# Connectors.net
KiCad netlist of a schematic drawn in Altium Designer
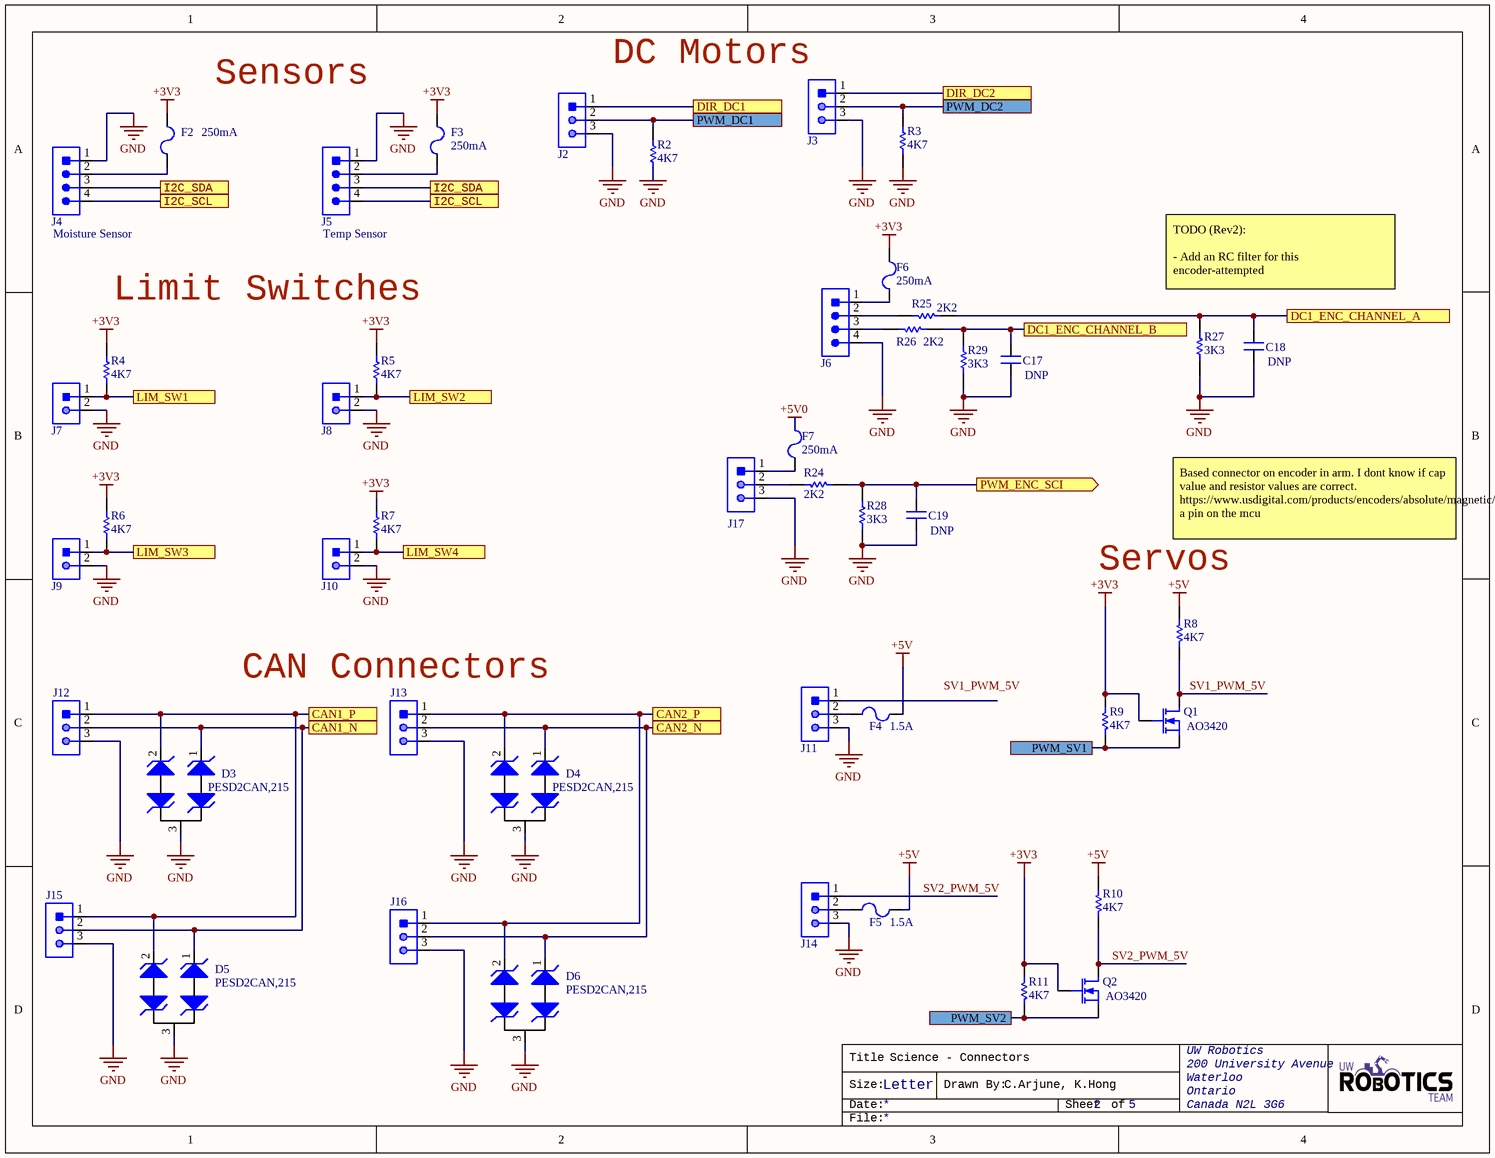
[diagram p0: Connectors.SchDoc]

(export (version "E")
  (design (tool "Eeschema 10.0.6"))
  (components
    (comp (ref "C17")
      (value "DNP")
      (footprint "CAPC0603(1608)55_N")
      (description "CAP CER 0.1UF 50V X7R 0603")
      (fields (field (name "MPN") "CC0603KRX7R9BB104") (field (name "MANUFACTURER") "Yageo"))
      (libsource (lib "UWRT_Schematic_Library_2020") (part "CAP_0.1uF_50V_0603"))
    )
    (comp (ref "C18")
      (value "DNP")
      (footprint "CAPC0603(1608)55_N")
      (description "CAP CER 0.1UF 50V X7R 0603")
      (fields (field (name "MPN") "CC0603KRX7R9BB104") (field (name "MANUFACTURER") "Yageo"))
      (libsource (lib "UWRT_Schematic_Library_2020") (part "CAP_0.1uF_50V_0603"))
    )
    (comp (ref "C19")
      (value "DNP")
      (footprint "CAPC0603(1608)55_N")
      (description "CAP CER 0.1UF 50V X7R 0603")
      (fields (field (name "MPN") "CC0603KRX7R9BB104") (field (name "MANUFACTURER") "Yageo"))
      (libsource (lib "UWRT_Schematic_Library_2020") (part "CAP_0.1uF_50V_0603"))
    )
    (comp (ref "D3")
      (value "TVS_DIODE_CAN")
      (footprint "TVS_DIODE_CAN")
      (description "TVS DIODE 24V 41V SOT323-3")
      (fields
        (field (name "MANUFACTURER") "Nexperia USA Inc.")
        (field (name "MANUFACTURER PART NUMBER") "PESD2CAN,215")
      )
      (libsource (lib "UWRT_Schematic_Library_2020") (part "TVS_DIODE_CAN"))
    )
    (comp (ref "D4")
      (value "TVS_DIODE_CAN")
      (footprint "TVS_DIODE_CAN")
      (description "TVS DIODE 24V 41V SOT323-3")
      (fields
        (field (name "MANUFACTURER") "Nexperia USA Inc.")
        (field (name "MANUFACTURER PART NUMBER") "PESD2CAN,215")
      )
      (libsource (lib "UWRT_Schematic_Library_2020") (part "TVS_DIODE_CAN"))
    )
    (comp (ref "D5")
      (value "TVS_DIODE_CAN")
      (footprint "TVS_DIODE_CAN")
      (description "TVS DIODE 24V 41V SOT323-3")
      (fields
        (field (name "MANUFACTURER") "Nexperia USA Inc.")
        (field (name "MANUFACTURER PART NUMBER") "PESD2CAN,215")
      )
      (libsource (lib "UWRT_Schematic_Library_2020") (part "TVS_DIODE_CAN"))
    )
    (comp (ref "D6")
      (value "TVS_DIODE_CAN")
      (footprint "TVS_DIODE_CAN")
      (description "TVS DIODE 24V 41V SOT323-3")
      (fields
        (field (name "MANUFACTURER") "Nexperia USA Inc.")
        (field (name "MANUFACTURER PART NUMBER") "PESD2CAN,215")
      )
      (libsource (lib "UWRT_Schematic_Library_2020") (part "TVS_DIODE_CAN"))
    )
    (comp (ref "F2")
      (value "FUSE_250mA_0603")
      (footprint "FUSE_0603")
      (description "FUSE SMD 250mA 32V")
      (fields (field (name "CURRENT RATING") "250mA"))
      (libsource (lib "UWRT_Schematic_Library_2020") (part "FUSE_250mA_0603"))
    )
    (comp (ref "F3")
      (value "FUSE_250mA_0603")
      (footprint "FUSE_0603")
      (description "FUSE SMD 250mA 32V")
      (fields (field (name "CURRENT RATING") "250mA"))
      (libsource (lib "UWRT_Schematic_Library_2020") (part "FUSE_250mA_0603"))
    )
    (comp (ref "F4")
      (value "FUSE_1.5A_0603")
      (footprint "FUSE_0603")
      (description "FUSE SMD 1.5A 32V")
      (fields (field (name "CURRENT RATING") "1.5A"))
      (libsource (lib "UWRT_Schematic_Library_2020") (part "FUSE_1.5A_0603"))
    )
    (comp (ref "F5")
      (value "FUSE_1.5A_0603")
      (footprint "FUSE_0603")
      (description "FUSE SMD 1.5A 32V")
      (fields (field (name "CURRENT RATING") "1.5A"))
      (libsource (lib "UWRT_Schematic_Library_2020") (part "FUSE_1.5A_0603"))
    )
    (comp (ref "F6")
      (value "FUSE_250mA_0603")
      (footprint "FUSE_0603")
      (description "FUSE SMD 250mA 32V")
      (fields (field (name "CURRENT RATING") "250mA"))
      (libsource (lib "UWRT_Schematic_Library_2020") (part "FUSE_250mA_0603"))
    )
    (comp (ref "F7")
      (value "FUSE_250mA_0603")
      (footprint "FUSE_0603")
      (description "FUSE SMD 250mA 32V")
      (fields (field (name "CURRENT RATING") "250mA"))
      (libsource (lib "UWRT_Schematic_Library_2020") (part "FUSE_250mA_0603"))
    )
    (comp (ref "J2")
      (value "CON_3M_SM4")
      (footprint "JST-B3B-SM4-TB")
      (description "CONN HEADER SMD 3POS 2MM")
      (fields
        (field (name "MANUFACTURER") "JST")
        (field (name "MANUFACTURER PART NUMBER") "B3B-PH-SM4-TB(LF)(SN)")
      )
      (libsource (lib "UWRT_Schematic_Library_2020") (part "CON_3M_SM4"))
    )
    (comp (ref "J3")
      (value "CON_3M_SM4")
      (footprint "JST-B3B-SM4-TB")
      (description "CONN HEADER SMD 3POS 2MM")
      (fields
        (field (name "MANUFACTURER") "JST")
        (field (name "MANUFACTURER PART NUMBER") "B3B-PH-SM4-TB(LF)(SN)")
      )
      (libsource (lib "UWRT_Schematic_Library_2020") (part "CON_3M_SM4"))
    )
    (comp (ref "J4")
      (value "Moisture Sensor")
      (footprint "JST-B4B-SM4-TB")
      (description "CONN HEADER SMD 4POS 2MM")
      (fields
        (field (name "MANUFACTURER") "JST")
        (field (name "MANUFACTURER PART NUMBER") "B4B-PH-SM4-TB(LF)(SN)")
      )
      (libsource (lib "UWRT_Schematic_Library_2020") (part "CON_4M_SM4"))
    )
    (comp (ref "J5")
      (value "Temp Sensor")
      (footprint "JST-B4B-SM4-TB")
      (description "CONN HEADER SMD 4POS 2MM")
      (fields
        (field (name "MANUFACTURER") "JST")
        (field (name "MANUFACTURER PART NUMBER") "B4B-PH-SM4-TB(LF)(SN)")
      )
      (libsource (lib "UWRT_Schematic_Library_2020") (part "CON_4M_SM4"))
    )
    (comp (ref "J6")
      (value "CON_4M_SM4")
      (footprint "JST-B4B-SM4-TB")
      (description "CONN HEADER SMD 4POS 2MM")
      (fields
        (field (name "MANUFACTURER") "JST")
        (field (name "MANUFACTURER PART NUMBER") "B4B-PH-SM4-TB(LF)(SN)")
      )
      (libsource (lib "UWRT_Schematic_Library_2020") (part "CON_4M_SM4"))
    )
    (comp (ref "J7")
      (value "CON_2M_SM4")
      (footprint "JST-B2B-SM4-TB")
      (description "CONN HEADER SMD 2POS 2MM")
      (fields
        (field (name "MANUFACTURER") "JST")
        (field (name "MANUFACTURER PART NUMBER") "B2B-PH-SM4-TB(LF)(SN)")
      )
      (libsource (lib "UWRT_Schematic_Library_2020") (part "CON_2M_SM4"))
    )
    (comp (ref "J8")
      (value "CON_2M_SM4")
      (footprint "JST-B2B-SM4-TB")
      (description "CONN HEADER SMD 2POS 2MM")
      (fields
        (field (name "MANUFACTURER") "JST")
        (field (name "MANUFACTURER PART NUMBER") "B2B-PH-SM4-TB(LF)(SN)")
      )
      (libsource (lib "UWRT_Schematic_Library_2020") (part "CON_2M_SM4"))
    )
    (comp (ref "J9")
      (value "CON_2M_SM4")
      (footprint "JST-B2B-SM4-TB")
      (description "CONN HEADER SMD 2POS 2MM")
      (fields
        (field (name "MANUFACTURER") "JST")
        (field (name "MANUFACTURER PART NUMBER") "B2B-PH-SM4-TB(LF)(SN)")
      )
      (libsource (lib "UWRT_Schematic_Library_2020") (part "CON_2M_SM4"))
    )
    (comp (ref "J10")
      (value "CON_2M_SM4")
      (footprint "JST-B2B-SM4-TB")
      (description "CONN HEADER SMD 2POS 2MM")
      (fields
        (field (name "MANUFACTURER") "JST")
        (field (name "MANUFACTURER PART NUMBER") "B2B-PH-SM4-TB(LF)(SN)")
      )
      (libsource (lib "UWRT_Schematic_Library_2020") (part "CON_2M_SM4"))
    )
    (comp (ref "J11")
      (value "CON_3M_SM4")
      (footprint "JST-B3B-SM4-TB")
      (description "CONN HEADER SMD 3POS 2MM")
      (fields
        (field (name "MANUFACTURER") "JST")
        (field (name "MANUFACTURER PART NUMBER") "B3B-PH-SM4-TB(LF)(SN)")
      )
      (libsource (lib "UWRT_Schematic_Library_2020") (part "CON_3M_SM4"))
    )
    (comp (ref "J12")
      (value "CON_3M_SM4")
      (footprint "JST-B3B-SM4-TB")
      (description "CONN HEADER SMD 3POS 2MM")
      (fields
        (field (name "MANUFACTURER") "JST")
        (field (name "MANUFACTURER PART NUMBER") "B3B-PH-SM4-TB(LF)(SN)")
      )
      (libsource (lib "UWRT_Schematic_Library_2020") (part "CON_3M_SM4"))
    )
    (comp (ref "J13")
      (value "CON_3M_SM4")
      (footprint "JST-B3B-SM4-TB")
      (description "CONN HEADER SMD 3POS 2MM")
      (fields
        (field (name "MANUFACTURER") "JST")
        (field (name "MANUFACTURER PART NUMBER") "B3B-PH-SM4-TB(LF)(SN)")
      )
      (libsource (lib "UWRT_Schematic_Library_2020") (part "CON_3M_SM4"))
    )
    (comp (ref "J14")
      (value "CON_3M_SM4")
      (footprint "JST-B3B-SM4-TB")
      (description "CONN HEADER SMD 3POS 2MM")
      (fields
        (field (name "MANUFACTURER") "JST")
        (field (name "MANUFACTURER PART NUMBER") "B3B-PH-SM4-TB(LF)(SN)")
      )
      (libsource (lib "UWRT_Schematic_Library_2020") (part "CON_3M_SM4"))
    )
    (comp (ref "J15")
      (value "CON_3M_SM4")
      (footprint "JST-B3B-SM4-TB")
      (description "CONN HEADER SMD 3POS 2MM")
      (fields
        (field (name "MANUFACTURER") "JST")
        (field (name "MANUFACTURER PART NUMBER") "B3B-PH-SM4-TB(LF)(SN)")
      )
      (libsource (lib "UWRT_Schematic_Library_2020") (part "CON_3M_SM4"))
    )
    (comp (ref "J16")
      (value "CON_3M_SM4")
      (footprint "JST-B3B-SM4-TB")
      (description "CONN HEADER SMD 3POS 2MM")
      (fields
        (field (name "MANUFACTURER") "JST")
        (field (name "MANUFACTURER PART NUMBER") "B3B-PH-SM4-TB(LF)(SN)")
      )
      (libsource (lib "UWRT_Schematic_Library_2020") (part "CON_3M_SM4"))
    )
    (comp (ref "J17")
      (value "CON_3M_SM4")
      (footprint "JST-B3B-SM4-TB")
      (description "CONN HEADER SMD 3POS 2MM")
      (fields
        (field (name "MANUFACTURER") "JST")
        (field (name "MANUFACTURER PART NUMBER") "B3B-PH-SM4-TB(LF)(SN)")
      )
      (libsource (lib "UWRT_Schematic_Library_2020") (part "CON_3M_SM4"))
    )
    (comp (ref "Q1")
      (value "NMOS_20V_6A")
      (footprint "NMOS_SOT23-3")
      (description "MOSFET N-CH 20V 6A SOT23")
      (fields (field (name "MPN") "AO3420") (field (name "MANUFACTURER") "Alpha & Omega"))
      (libsource (lib "UWRT_Schematic_Library_2020") (part "NMOS_20V_6A"))
    )
    (comp (ref "Q2")
      (value "NMOS_20V_6A")
      (footprint "NMOS_SOT23-3")
      (description "MOSFET N-CH 20V 6A SOT23")
      (fields (field (name "MPN") "AO3420") (field (name "MANUFACTURER") "Alpha & Omega"))
      (libsource (lib "UWRT_Schematic_Library_2020") (part "NMOS_20V_6A"))
    )
    (comp (ref "R2")
      (value "4K7")
      (footprint "RESC0603(1608)_N")
      (description "RES SMD 4.7K OHM 5% 1/10W 0603")
      (fields (field (name "MANUFACTURER") "Yageo") (field (name "MPN") "RC0603JR-074K7L"))
      (libsource (lib "UWRT_Schematic_Library_2020") (part "RES_4K7_0603"))
    )
    (comp (ref "R3")
      (value "4K7")
      (footprint "RESC0603(1608)_N")
      (description "RES SMD 4.7K OHM 5% 1/10W 0603")
      (fields (field (name "MANUFACTURER") "Yageo") (field (name "MPN") "RC0603JR-074K7L"))
      (libsource (lib "UWRT_Schematic_Library_2020") (part "RES_4K7_0603"))
    )
    (comp (ref "R4")
      (value "4K7")
      (footprint "RESC0603(1608)_N")
      (description "RES SMD 4.7K OHM 5% 1/10W 0603")
      (fields (field (name "MANUFACTURER") "Yageo") (field (name "MPN") "RC0603JR-074K7L"))
      (libsource (lib "UWRT_Schematic_Library_2020") (part "RES_4K7_0603"))
    )
    (comp (ref "R5")
      (value "4K7")
      (footprint "RESC0603(1608)_N")
      (description "RES SMD 4.7K OHM 5% 1/10W 0603")
      (fields (field (name "MANUFACTURER") "Yageo") (field (name "MPN") "RC0603JR-074K7L"))
      (libsource (lib "UWRT_Schematic_Library_2020") (part "RES_4K7_0603"))
    )
    (comp (ref "R6")
      (value "4K7")
      (footprint "RESC0603(1608)_N")
      (description "RES SMD 4.7K OHM 5% 1/10W 0603")
      (fields (field (name "MANUFACTURER") "Yageo") (field (name "MPN") "RC0603JR-074K7L"))
      (libsource (lib "UWRT_Schematic_Library_2020") (part "RES_4K7_0603"))
    )
    (comp (ref "R7")
      (value "4K7")
      (footprint "RESC0603(1608)_N")
      (description "RES SMD 4.7K OHM 5% 1/10W 0603")
      (fields (field (name "MANUFACTURER") "Yageo") (field (name "MPN") "RC0603JR-074K7L"))
      (libsource (lib "UWRT_Schematic_Library_2020") (part "RES_4K7_0603"))
    )
    (comp (ref "R8")
      (value "4K7")
      (footprint "RESC0603(1608)_N")
      (description "RES SMD 4.7K OHM 5% 1/10W 0603")
      (fields (field (name "MANUFACTURER") "Yageo") (field (name "MPN") "RC0603JR-074K7L"))
      (libsource (lib "UWRT_Schematic_Library_2020") (part "RES_4K7_0603"))
    )
    (comp (ref "R9")
      (value "4K7")
      (footprint "RESC0603(1608)_N")
      (description "RES SMD 4.7K OHM 5% 1/10W 0603")
      (fields (field (name "MANUFACTURER") "Yageo") (field (name "MPN") "RC0603JR-074K7L"))
      (libsource (lib "UWRT_Schematic_Library_2020") (part "RES_4K7_0603"))
    )
    (comp (ref "R10")
      (value "4K7")
      (footprint "RESC0603(1608)_N")
      (description "RES SMD 4.7K OHM 5% 1/10W 0603")
      (fields (field (name "MANUFACTURER") "Yageo") (field (name "MPN") "RC0603JR-074K7L"))
      (libsource (lib "UWRT_Schematic_Library_2020") (part "RES_4K7_0603"))
    )
    (comp (ref "R11")
      (value "4K7")
      (footprint "RESC0603(1608)_N")
      (description "RES SMD 4.7K OHM 5% 1/10W 0603")
      (fields (field (name "MANUFACTURER") "Yageo") (field (name "MPN") "RC0603JR-074K7L"))
      (libsource (lib "UWRT_Schematic_Library_2020") (part "RES_4K7_0603"))
    )
    (comp (ref "R24")
      (value "2K2")
      (footprint "RESC0603(1608)_N")
      (description "RES SMD 2.2K OHM 1% 1/10W 0603")
      (fields (field (name "MANUFACTURER") "Yageo") (field (name "TOLERANCE") "1%"))
      (libsource (lib "UWRT_Schematic_Library_2020") (part "RES_2K2_0603"))
    )
    (comp (ref "R25")
      (value "2K2")
      (footprint "RESC0603(1608)_N")
      (description "RES SMD 2.2K OHM 1% 1/10W 0603")
      (fields (field (name "MANUFACTURER") "Yageo") (field (name "TOLERANCE") "1%"))
      (libsource (lib "UWRT_Schematic_Library_2020") (part "RES_2K2_0603"))
    )
    (comp (ref "R26")
      (value "2K2")
      (footprint "RESC0603(1608)_N")
      (description "RES SMD 2.2K OHM 1% 1/10W 0603")
      (fields (field (name "MANUFACTURER") "Yageo") (field (name "TOLERANCE") "1%"))
      (libsource (lib "UWRT_Schematic_Library_2020") (part "RES_2K2_0603"))
    )
    (comp (ref "R27")
      (value "3K3")
      (footprint "RESC0603(1608)_N")
      (description "RES SMD 3.3K OHM 5% 1/10W 0603")
      (fields (field (name "MANUFACTURER") "Yageo") (field (name "TOLERANCE") "5%"))
      (libsource (lib "UWRT_Schematic_Library_2020") (part "RES_3K3_0603"))
    )
    (comp (ref "R28")
      (value "3K3")
      (footprint "RESC0603(1608)_N")
      (description "RES SMD 3.3K OHM 5% 1/10W 0603")
      (fields (field (name "MANUFACTURER") "Yageo") (field (name "TOLERANCE") "5%"))
      (libsource (lib "UWRT_Schematic_Library_2020") (part "RES_3K3_0603"))
    )
    (comp (ref "R29")
      (value "3K3")
      (footprint "RESC0603(1608)_N")
      (description "RES SMD 3.3K OHM 5% 1/10W 0603")
      (fields (field (name "MANUFACTURER") "Yageo") (field (name "TOLERANCE") "5%"))
      (libsource (lib "UWRT_Schematic_Library_2020") (part "RES_3K3_0603"))
    )
  )
  (nets
    (net (code "1") (name "+3V3") (class "Default")
      (node (ref "F2") (pin "1") (pinfunction "1_1") (pintype "passive"))
      (node (ref "F3") (pin "1") (pinfunction "1_1") (pintype "passive"))
      (node (ref "F6") (pin "2") (pinfunction "2_2") (pintype "passive"))
      (node (ref "Q1") (pin "1") (pinfunction "G_1") (pintype "passive"))
      (node (ref "Q2") (pin "1") (pinfunction "G_1") (pintype "passive"))
      (node (ref "R11") (pin "2") (pinfunction "2_2") (pintype "passive"))
      (node (ref "R4") (pin "2") (pinfunction "2_2") (pintype "passive"))
      (node (ref "R5") (pin "2") (pinfunction "2_2") (pintype "passive"))
      (node (ref "R6") (pin "2") (pinfunction "2_2") (pintype "passive"))
      (node (ref "R7") (pin "2") (pinfunction "2_2") (pintype "passive"))
      (node (ref "R9") (pin "2") (pinfunction "2_2") (pintype "passive"))
    )
    (net (code "2") (name "+5V") (class "Default")
      (node (ref "F4") (pin "1") (pinfunction "1_1") (pintype "passive"))
      (node (ref "F5") (pin "1") (pinfunction "1_1") (pintype "passive"))
      (node (ref "R10") (pin "2") (pinfunction "2_2") (pintype "passive"))
      (node (ref "R8") (pin "2") (pinfunction "2_2") (pintype "passive"))
    )
    (net (code "3") (name "+5V0") (class "Default")
      (node (ref "F7") (pin "2") (pinfunction "2_2") (pintype "passive"))
    )
    (net (code "4") (name "/CAN1_N") (class "Default")
      (node (ref "D3") (pin "1") (pinfunction "1_1") (pintype "passive"))
      (node (ref "D5") (pin "1") (pinfunction "1_1") (pintype "passive"))
      (node (ref "J12") (pin "2") (pinfunction "2_2") (pintype "passive"))
      (node (ref "J15") (pin "2") (pinfunction "2_2") (pintype "passive"))
    )
    (net (code "5") (name "/CAN1_P") (class "Default")
      (node (ref "D3") (pin "2") (pinfunction "2_2") (pintype "passive"))
      (node (ref "D5") (pin "2") (pinfunction "2_2") (pintype "passive"))
      (node (ref "J12") (pin "1") (pinfunction "1_1") (pintype "passive"))
      (node (ref "J15") (pin "1") (pinfunction "1_1") (pintype "passive"))
    )
    (net (code "6") (name "/CAN2_N") (class "Default")
      (node (ref "D4") (pin "1") (pinfunction "1_1") (pintype "passive"))
      (node (ref "D6") (pin "1") (pinfunction "1_1") (pintype "passive"))
      (node (ref "J13") (pin "2") (pinfunction "2_2") (pintype "passive"))
      (node (ref "J16") (pin "2") (pinfunction "2_2") (pintype "passive"))
    )
    (net (code "7") (name "/CAN2_P") (class "Default")
      (node (ref "D4") (pin "2") (pinfunction "2_2") (pintype "passive"))
      (node (ref "D6") (pin "2") (pinfunction "2_2") (pintype "passive"))
      (node (ref "J13") (pin "1") (pinfunction "1_1") (pintype "passive"))
      (node (ref "J16") (pin "1") (pinfunction "1_1") (pintype "passive"))
    )
    (net (code "8") (name "/DC1_ENC_CHANNEL_A") (class "Default")
      (node (ref "C18") (pin "2") (pinfunction "2_2") (pintype "passive"))
      (node (ref "R25") (pin "1") (pinfunction "1_1") (pintype "passive"))
      (node (ref "R27") (pin "2") (pinfunction "2_2") (pintype "passive"))
    )
    (net (code "9") (name "/DC1_ENC_CHANNEL_B") (class "Default")
      (node (ref "C17") (pin "2") (pinfunction "2_2") (pintype "passive"))
      (node (ref "R26") (pin "1") (pinfunction "1_1") (pintype "passive"))
      (node (ref "R29") (pin "2") (pinfunction "2_2") (pintype "passive"))
    )
    (net (code "10") (name "/DIR_DC1") (class "Default")
      (node (ref "J2") (pin "1") (pinfunction "1_1") (pintype "passive"))
    )
    (net (code "11") (name "/DIR_DC2") (class "Default")
      (node (ref "J3") (pin "1") (pinfunction "1_1") (pintype "passive"))
    )
    (net (code "12") (name "/I2C_SCL") (class "Default")
      (node (ref "J4") (pin "4") (pinfunction "4_4") (pintype "passive"))
      (node (ref "J5") (pin "4") (pinfunction "4_4") (pintype "passive"))
    )
    (net (code "13") (name "/I2C_SDA") (class "Default")
      (node (ref "J4") (pin "3") (pinfunction "3_3") (pintype "passive"))
      (node (ref "J5") (pin "3") (pinfunction "3_3") (pintype "passive"))
    )
    (net (code "14") (name "/LIM_SW1") (class "Default")
      (node (ref "J7") (pin "1") (pinfunction "1_1") (pintype "passive"))
      (node (ref "R4") (pin "1") (pinfunction "1_1") (pintype "passive"))
    )
    (net (code "15") (name "/LIM_SW2") (class "Default")
      (node (ref "J8") (pin "1") (pinfunction "1_1") (pintype "passive"))
      (node (ref "R5") (pin "1") (pinfunction "1_1") (pintype "passive"))
    )
    (net (code "16") (name "/LIM_SW3") (class "Default")
      (node (ref "J9") (pin "1") (pinfunction "1_1") (pintype "passive"))
      (node (ref "R6") (pin "1") (pinfunction "1_1") (pintype "passive"))
    )
    (net (code "17") (name "/LIM_SW4") (class "Default")
      (node (ref "J10") (pin "1") (pinfunction "1_1") (pintype "passive"))
      (node (ref "R7") (pin "1") (pinfunction "1_1") (pintype "passive"))
    )
    (net (code "18") (name "/PWM_DC1") (class "Default")
      (node (ref "J2") (pin "2") (pinfunction "2_2") (pintype "passive"))
      (node (ref "R2") (pin "1") (pinfunction "1_1") (pintype "passive"))
    )
    (net (code "19") (name "/PWM_DC2") (class "Default")
      (node (ref "J3") (pin "2") (pinfunction "2_2") (pintype "passive"))
      (node (ref "R3") (pin "1") (pinfunction "1_1") (pintype "passive"))
    )
    (net (code "20") (name "/PWM_ENC_SCI") (class "Default")
      (node (ref "C19") (pin "2") (pinfunction "2_2") (pintype "passive"))
      (node (ref "R24") (pin "1") (pinfunction "1_1") (pintype "passive"))
      (node (ref "R28") (pin "2") (pinfunction "2_2") (pintype "passive"))
    )
    (net (code "21") (name "/PWM_SV1") (class "Default")
      (node (ref "Q1") (pin "2") (pinfunction "S_2") (pintype "passive"))
      (node (ref "R9") (pin "1") (pinfunction "1_1") (pintype "passive"))
    )
    (net (code "22") (name "/PWM_SV2") (class "Default")
      (node (ref "Q2") (pin "2") (pinfunction "S_2") (pintype "passive"))
      (node (ref "R11") (pin "1") (pinfunction "1_1") (pintype "passive"))
    )
    (net (code "23") (name "/SV1_PWM_5V") (class "Default")
      (node (ref "Q1") (pin "3") (pinfunction "D_3") (pintype "passive"))
      (node (ref "R8") (pin "1") (pinfunction "1_1") (pintype "passive"))
    )
    (net (code "24") (name "/SV2_PWM_5V") (class "Default")
      (node (ref "J14") (pin "1") (pinfunction "1_1") (pintype "passive"))
      (node (ref "Q2") (pin "3") (pinfunction "D_3") (pintype "passive"))
      (node (ref "R10") (pin "1") (pinfunction "1_1") (pintype "passive"))
    )
    (net (code "25") (name "GND") (class "Default")
      (node (ref "C17") (pin "1") (pinfunction "1_1") (pintype "passive"))
      (node (ref "C18") (pin "1") (pinfunction "1_1") (pintype "passive"))
      (node (ref "C19") (pin "1") (pinfunction "1_1") (pintype "passive"))
      (node (ref "D3") (pin "3") (pinfunction "3_3") (pintype "passive"))
      (node (ref "D4") (pin "3") (pinfunction "3_3") (pintype "passive"))
      (node (ref "D5") (pin "3") (pinfunction "3_3") (pintype "passive"))
      (node (ref "D6") (pin "3") (pinfunction "3_3") (pintype "passive"))
      (node (ref "J10") (pin "2") (pinfunction "2_2") (pintype "passive"))
      (node (ref "J11") (pin "3") (pinfunction "3_3") (pintype "passive"))
      (node (ref "J12") (pin "3") (pinfunction "3_3") (pintype "passive"))
      (node (ref "J13") (pin "3") (pinfunction "3_3") (pintype "passive"))
      (node (ref "J14") (pin "3") (pinfunction "3_3") (pintype "passive"))
      (node (ref "J15") (pin "3") (pinfunction "3_3") (pintype "passive"))
      (node (ref "J16") (pin "3") (pinfunction "3_3") (pintype "passive"))
      (node (ref "J17") (pin "3") (pinfunction "3_3") (pintype "passive"))
      (node (ref "J2") (pin "3") (pinfunction "3_3") (pintype "passive"))
      (node (ref "J3") (pin "3") (pinfunction "3_3") (pintype "passive"))
      (node (ref "J4") (pin "1") (pinfunction "1_1") (pintype "passive"))
      (node (ref "J5") (pin "1") (pinfunction "1_1") (pintype "passive"))
      (node (ref "J6") (pin "4") (pinfunction "4_4") (pintype "passive"))
      (node (ref "J7") (pin "2") (pinfunction "2_2") (pintype "passive"))
      (node (ref "J8") (pin "2") (pinfunction "2_2") (pintype "passive"))
      (node (ref "J9") (pin "2") (pinfunction "2_2") (pintype "passive"))
      (node (ref "R2") (pin "2") (pinfunction "2_2") (pintype "passive"))
      (node (ref "R27") (pin "1") (pinfunction "1_1") (pintype "passive"))
      (node (ref "R28") (pin "1") (pinfunction "1_1") (pintype "passive"))
      (node (ref "R29") (pin "1") (pinfunction "1_1") (pintype "passive"))
      (node (ref "R3") (pin "2") (pinfunction "2_2") (pintype "passive"))
    )
    (net (code "26") (name "Net-(F2-Pad2)") (class "Default")
      (node (ref "F2") (pin "2") (pinfunction "2_2") (pintype "passive"))
      (node (ref "J4") (pin "2") (pinfunction "2_2") (pintype "passive"))
    )
    (net (code "27") (name "Net-(F3-Pad2)") (class "Default")
      (node (ref "F3") (pin "2") (pinfunction "2_2") (pintype "passive"))
      (node (ref "J5") (pin "2") (pinfunction "2_2") (pintype "passive"))
    )
    (net (code "28") (name "Net-(F4-Pad2)") (class "Default")
      (node (ref "F4") (pin "2") (pinfunction "2_2") (pintype "passive"))
      (node (ref "J11") (pin "2") (pinfunction "2_2") (pintype "passive"))
    )
    (net (code "29") (name "Net-(F5-Pad2)") (class "Default")
      (node (ref "F5") (pin "2") (pinfunction "2_2") (pintype "passive"))
      (node (ref "J14") (pin "2") (pinfunction "2_2") (pintype "passive"))
    )
    (net (code "30") (name "Net-(F6-Pad1)") (class "Default")
      (node (ref "F6") (pin "1") (pinfunction "1_1") (pintype "passive"))
      (node (ref "J6") (pin "1") (pinfunction "1_1") (pintype "passive"))
    )
    (net (code "31") (name "Net-(F7-Pad1)") (class "Default")
      (node (ref "F7") (pin "1") (pinfunction "1_1") (pintype "passive"))
      (node (ref "J17") (pin "1") (pinfunction "1_1") (pintype "passive"))
    )
    (net (code "32") (name "Net-(J6-Pad2)") (class "Default")
      (node (ref "J6") (pin "2") (pinfunction "2_2") (pintype "passive"))
      (node (ref "R25") (pin "2") (pinfunction "2_2") (pintype "passive"))
    )
    (net (code "33") (name "Net-(J6-Pad3)") (class "Default")
      (node (ref "J6") (pin "3") (pinfunction "3_3") (pintype "passive"))
      (node (ref "R26") (pin "2") (pinfunction "2_2") (pintype "passive"))
    )
    (net (code "34") (name "Net-(J17-Pad2)") (class "Default")
      (node (ref "J17") (pin "2") (pinfunction "2_2") (pintype "passive"))
      (node (ref "R24") (pin "2") (pinfunction "2_2") (pintype "passive"))
    )
    (net (code "35") (name "unconnected-(J11-Pad1)") (class "Default")
      (node (ref "J11") (pin "1") (pinfunction "1_1") (pintype "passive"))
    )
  )
)
